# BarGraphDriver.net
KiCad netlist of a schematic drawn in EAGLE
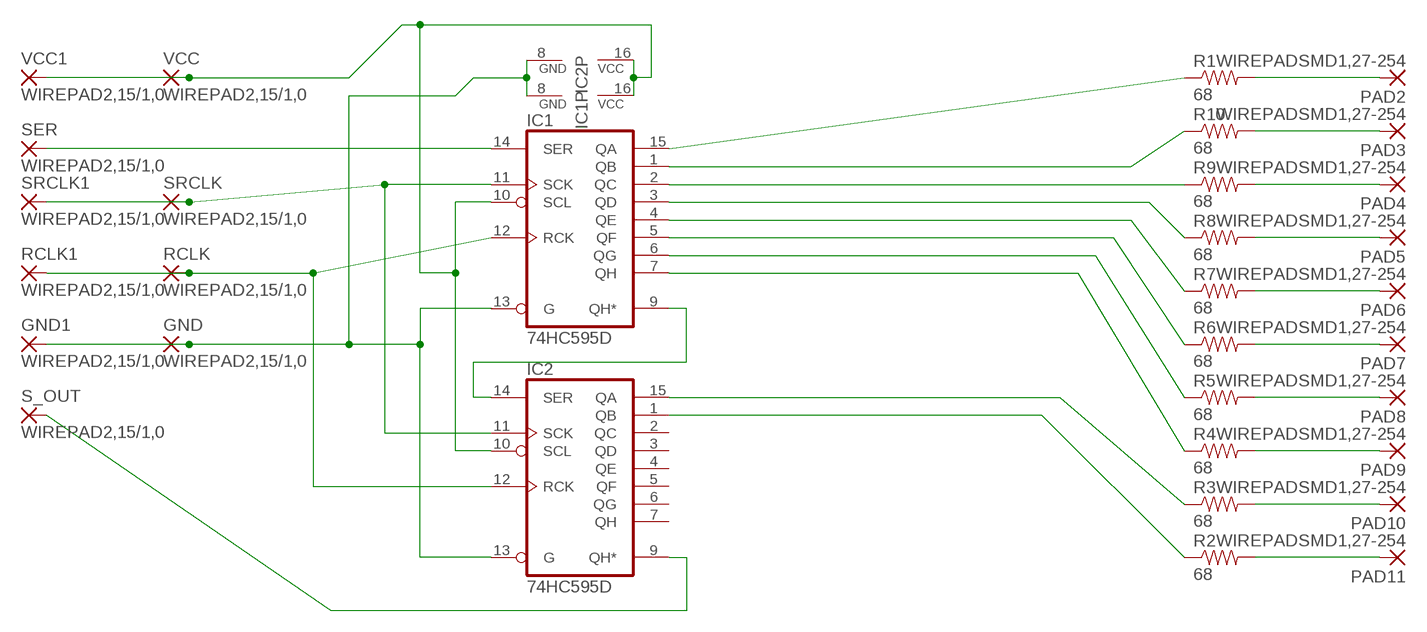
[diagram p0: schematic, sheet 1]

(export (version "E")
  (design (tool "Eeschema 10.0.6"))
  (components
    (comp (ref "GND")
      (value "WIREPAD2,15/1,0")
      (footprint "eagle-import:2,15_1,0")
      (libsource (lib "eagle-import") (part "wirepad_WIREPAD2,15/1,0"))
    )
    (comp (ref "GND1")
      (value "WIREPAD2,15/1,0")
      (footprint "eagle-import:2,15_1,0")
      (libsource (lib "eagle-import") (part "wirepad_WIREPAD2,15/1,0"))
    )
    (comp (ref "IC1")
      (value "74HC595D")
      (footprint "eagle-import:SO16")
      (libsource (lib "eagle-import") (part "74595DHC"))
    )
    (comp (ref "IC2")
      (value "74HC595D")
      (footprint "eagle-import:SO16")
      (libsource (lib "eagle-import") (part "74595DHC"))
    )
    (comp (ref "PAD2")
      (value "WIREPADSMD1,27-254")
      (footprint "eagle-import:SMD1,27-2,54")
      (libsource (lib "eagle-import") (part "wirepad_WIREPADSMD1,27-254"))
    )
    (comp (ref "PAD3")
      (value "WIREPADSMD1,27-254")
      (footprint "eagle-import:SMD1,27-2,54")
      (libsource (lib "eagle-import") (part "wirepad_WIREPADSMD1,27-254"))
    )
    (comp (ref "PAD4")
      (value "WIREPADSMD1,27-254")
      (footprint "eagle-import:SMD1,27-2,54")
      (libsource (lib "eagle-import") (part "wirepad_WIREPADSMD1,27-254"))
    )
    (comp (ref "PAD5")
      (value "WIREPADSMD1,27-254")
      (footprint "eagle-import:SMD1,27-2,54")
      (libsource (lib "eagle-import") (part "wirepad_WIREPADSMD1,27-254"))
    )
    (comp (ref "PAD6")
      (value "WIREPADSMD1,27-254")
      (footprint "eagle-import:SMD1,27-2,54")
      (libsource (lib "eagle-import") (part "wirepad_WIREPADSMD1,27-254"))
    )
    (comp (ref "PAD7")
      (value "WIREPADSMD1,27-254")
      (footprint "eagle-import:SMD1,27-2,54")
      (libsource (lib "eagle-import") (part "wirepad_WIREPADSMD1,27-254"))
    )
    (comp (ref "PAD8")
      (value "WIREPADSMD1,27-254")
      (footprint "eagle-import:SMD1,27-2,54")
      (libsource (lib "eagle-import") (part "wirepad_WIREPADSMD1,27-254"))
    )
    (comp (ref "PAD9")
      (value "WIREPADSMD1,27-254")
      (footprint "eagle-import:SMD1,27-2,54")
      (libsource (lib "eagle-import") (part "wirepad_WIREPADSMD1,27-254"))
    )
    (comp (ref "PAD10")
      (value "WIREPADSMD1,27-254")
      (footprint "eagle-import:SMD1,27-2,54")
      (libsource (lib "eagle-import") (part "wirepad_WIREPADSMD1,27-254"))
    )
    (comp (ref "PAD11")
      (value "WIREPADSMD1,27-254")
      (footprint "eagle-import:SMD1,27-2,54")
      (libsource (lib "eagle-import") (part "wirepad_WIREPADSMD1,27-254"))
    )
    (comp (ref "R1")
      (value "68")
      (footprint "eagle-import:1206")
      (libsource (lib "eagle-import") (part "RESISTOR1206"))
    )
    (comp (ref "R2")
      (value "68")
      (footprint "eagle-import:1206")
      (libsource (lib "eagle-import") (part "RESISTOR1206"))
    )
    (comp (ref "R3")
      (value "68")
      (footprint "eagle-import:1206")
      (libsource (lib "eagle-import") (part "RESISTOR1206"))
    )
    (comp (ref "R4")
      (value "68")
      (footprint "eagle-import:1206")
      (libsource (lib "eagle-import") (part "RESISTOR1206"))
    )
    (comp (ref "R5")
      (value "68")
      (footprint "eagle-import:1206")
      (libsource (lib "eagle-import") (part "RESISTOR1206"))
    )
    (comp (ref "R6")
      (value "68")
      (footprint "eagle-import:1206")
      (libsource (lib "eagle-import") (part "RESISTOR1206"))
    )
    (comp (ref "R7")
      (value "68")
      (footprint "eagle-import:1206")
      (libsource (lib "eagle-import") (part "RESISTOR1206"))
    )
    (comp (ref "R8")
      (value "68")
      (footprint "eagle-import:1206")
      (libsource (lib "eagle-import") (part "RESISTOR1206"))
    )
    (comp (ref "R9")
      (value "68")
      (footprint "eagle-import:1206")
      (libsource (lib "eagle-import") (part "RESISTOR1206"))
    )
    (comp (ref "R10")
      (value "68")
      (footprint "eagle-import:1206")
      (libsource (lib "eagle-import") (part "RESISTOR1206"))
    )
    (comp (ref "RCLK")
      (value "WIREPAD2,15/1,0")
      (footprint "eagle-import:2,15_1,0")
      (libsource (lib "eagle-import") (part "wirepad_WIREPAD2,15/1,0"))
    )
    (comp (ref "RCLK1")
      (value "WIREPAD2,15/1,0")
      (footprint "eagle-import:2,15_1,0")
      (libsource (lib "eagle-import") (part "wirepad_WIREPAD2,15/1,0"))
    )
    (comp (ref "SER")
      (value "WIREPAD2,15/1,0")
      (footprint "eagle-import:2,15_1,0")
      (libsource (lib "eagle-import") (part "wirepad_WIREPAD2,15/1,0"))
    )
    (comp (ref "SRCLK")
      (value "WIREPAD2,15/1,0")
      (footprint "eagle-import:2,15_1,0")
      (libsource (lib "eagle-import") (part "wirepad_WIREPAD2,15/1,0"))
    )
    (comp (ref "SRCLK1")
      (value "WIREPAD2,15/1,0")
      (footprint "eagle-import:2,15_1,0")
      (libsource (lib "eagle-import") (part "wirepad_WIREPAD2,15/1,0"))
    )
    (comp (ref "S_OUT")
      (value "WIREPAD2,15/1,0")
      (footprint "eagle-import:2,15_1,0")
      (libsource (lib "eagle-import") (part "wirepad_WIREPAD2,15/1,0"))
    )
    (comp (ref "VCC")
      (value "WIREPAD2,15/1,0")
      (footprint "eagle-import:2,15_1,0")
      (libsource (lib "eagle-import") (part "WIREPAD2,15/1,0"))
    )
    (comp (ref "VCC1")
      (value "WIREPAD2,15/1,0")
      (footprint "eagle-import:2,15_1,0")
      (libsource (lib "eagle-import") (part "WIREPAD2,15/1,0"))
    )
  )
  (nets
    (net (code "1") (name "Net-(GND-P)") (class "Default")
      (node (ref "GND") (pin "1") (pinfunction "P_1") (pintype "passive"))
      (node (ref "GND1") (pin "1") (pinfunction "P_1") (pintype "passive"))
      (node (ref "IC1") (pin "13") (pinfunction "G_13") (pintype "input"))
      (node (ref "IC1") (pin "8") (pinfunction "GND_8") (pintype "power_in"))
      (node (ref "IC2") (pin "13") (pinfunction "G_13") (pintype "input"))
      (node (ref "IC2") (pin "8") (pinfunction "GND_8") (pintype "power_in"))
    )
    (net (code "2") (name "Net-(IC1A-QA)") (class "Default")
      (node (ref "IC1") (pin "15") (pinfunction "QA_15") (pintype "tri_state"))
      (node (ref "R1") (pin "1") (pinfunction "1_1") (pintype "passive"))
    )
    (net (code "3") (name "Net-(IC1A-QB)") (class "Default")
      (node (ref "IC1") (pin "1") (pinfunction "QB_1") (pintype "tri_state"))
      (node (ref "R10") (pin "1") (pinfunction "1_1") (pintype "passive"))
    )
    (net (code "4") (name "Net-(IC1A-QC)") (class "Default")
      (node (ref "IC1") (pin "2") (pinfunction "QC_2") (pintype "tri_state"))
      (node (ref "R9") (pin "1") (pinfunction "1_1") (pintype "passive"))
    )
    (net (code "5") (name "Net-(IC1A-QD)") (class "Default")
      (node (ref "IC1") (pin "3") (pinfunction "QD_3") (pintype "tri_state"))
      (node (ref "R8") (pin "1") (pinfunction "1_1") (pintype "passive"))
    )
    (net (code "6") (name "Net-(IC1A-QE)") (class "Default")
      (node (ref "IC1") (pin "4") (pinfunction "QE_4") (pintype "tri_state"))
      (node (ref "R7") (pin "1") (pinfunction "1_1") (pintype "passive"))
    )
    (net (code "7") (name "Net-(IC1A-QF)") (class "Default")
      (node (ref "IC1") (pin "5") (pinfunction "QF_5") (pintype "tri_state"))
      (node (ref "R6") (pin "1") (pinfunction "1_1") (pintype "passive"))
    )
    (net (code "8") (name "Net-(IC1A-QG)") (class "Default")
      (node (ref "IC1") (pin "6") (pinfunction "QG_6") (pintype "tri_state"))
      (node (ref "R5") (pin "1") (pinfunction "1_1") (pintype "passive"))
    )
    (net (code "9") (name "Net-(IC1A-QH)") (class "Default")
      (node (ref "IC1") (pin "7") (pinfunction "QH_7") (pintype "tri_state"))
      (node (ref "R4") (pin "1") (pinfunction "1_1") (pintype "passive"))
    )
    (net (code "10") (name "Net-(IC1A-QH*)") (class "Default")
      (node (ref "IC1") (pin "9") (pinfunction "QH*_9") (pintype "tri_state"))
      (node (ref "IC2") (pin "14") (pinfunction "SER_14") (pintype "input"))
    )
    (net (code "11") (name "Net-(IC1A-RCK)") (class "Default")
      (node (ref "IC1") (pin "12") (pinfunction "RCK_12") (pintype "input"))
      (node (ref "IC2") (pin "12") (pinfunction "RCK_12") (pintype "input"))
      (node (ref "RCLK") (pin "1") (pinfunction "P_1") (pintype "passive"))
      (node (ref "RCLK1") (pin "1") (pinfunction "P_1") (pintype "passive"))
    )
    (net (code "12") (name "Net-(IC1A-SCK)") (class "Default")
      (node (ref "IC1") (pin "11") (pinfunction "SCK_11") (pintype "input"))
      (node (ref "IC2") (pin "11") (pinfunction "SCK_11") (pintype "input"))
      (node (ref "SRCLK") (pin "1") (pinfunction "P_1") (pintype "passive"))
      (node (ref "SRCLK1") (pin "1") (pinfunction "P_1") (pintype "passive"))
    )
    (net (code "13") (name "Net-(IC1A-SCL)") (class "Default")
      (node (ref "IC1") (pin "10") (pinfunction "SCL_10") (pintype "input"))
      (node (ref "IC1") (pin "16") (pinfunction "VCC_16") (pintype "power_in"))
      (node (ref "IC2") (pin "10") (pinfunction "SCL_10") (pintype "input"))
      (node (ref "IC2") (pin "16") (pinfunction "VCC_16") (pintype "power_in"))
      (node (ref "VCC") (pin "1") (pinfunction "P_1") (pintype "passive"))
      (node (ref "VCC1") (pin "1") (pinfunction "P_1") (pintype "passive"))
    )
    (net (code "14") (name "Net-(IC1A-SER)") (class "Default")
      (node (ref "IC1") (pin "14") (pinfunction "SER_14") (pintype "input"))
      (node (ref "SER") (pin "1") (pinfunction "P_1") (pintype "passive"))
    )
    (net (code "15") (name "Net-(IC2A-QA)") (class "Default")
      (node (ref "IC2") (pin "15") (pinfunction "QA_15") (pintype "tri_state"))
      (node (ref "R3") (pin "1") (pinfunction "1_1") (pintype "passive"))
    )
    (net (code "16") (name "Net-(IC2A-QB)") (class "Default")
      (node (ref "IC2") (pin "1") (pinfunction "QB_1") (pintype "tri_state"))
      (node (ref "R2") (pin "1") (pinfunction "1_1") (pintype "passive"))
    )
    (net (code "17") (name "Net-(IC2A-QH*)") (class "Default")
      (node (ref "IC2") (pin "9") (pinfunction "QH*_9") (pintype "tri_state"))
      (node (ref "S_OUT") (pin "1") (pinfunction "P_1") (pintype "passive"))
    )
    (net (code "18") (name "Net-(PAD2-P)") (class "Default")
      (node (ref "PAD2") (pin "1") (pinfunction "P_1") (pintype "passive"))
      (node (ref "R1") (pin "2") (pinfunction "2_2") (pintype "passive"))
    )
    (net (code "19") (name "Net-(PAD3-P)") (class "Default")
      (node (ref "PAD3") (pin "1") (pinfunction "P_1") (pintype "passive"))
      (node (ref "R10") (pin "2") (pinfunction "2_2") (pintype "passive"))
    )
    (net (code "20") (name "Net-(PAD4-P)") (class "Default")
      (node (ref "PAD4") (pin "1") (pinfunction "P_1") (pintype "passive"))
      (node (ref "R9") (pin "2") (pinfunction "2_2") (pintype "passive"))
    )
    (net (code "21") (name "Net-(PAD5-P)") (class "Default")
      (node (ref "PAD5") (pin "1") (pinfunction "P_1") (pintype "passive"))
      (node (ref "R8") (pin "2") (pinfunction "2_2") (pintype "passive"))
    )
    (net (code "22") (name "Net-(PAD6-P)") (class "Default")
      (node (ref "PAD6") (pin "1") (pinfunction "P_1") (pintype "passive"))
      (node (ref "R7") (pin "2") (pinfunction "2_2") (pintype "passive"))
    )
    (net (code "23") (name "Net-(PAD7-P)") (class "Default")
      (node (ref "PAD7") (pin "1") (pinfunction "P_1") (pintype "passive"))
      (node (ref "R6") (pin "2") (pinfunction "2_2") (pintype "passive"))
    )
    (net (code "24") (name "Net-(PAD8-P)") (class "Default")
      (node (ref "PAD8") (pin "1") (pinfunction "P_1") (pintype "passive"))
      (node (ref "R5") (pin "2") (pinfunction "2_2") (pintype "passive"))
    )
    (net (code "25") (name "Net-(PAD9-P)") (class "Default")
      (node (ref "PAD9") (pin "1") (pinfunction "P_1") (pintype "passive"))
      (node (ref "R4") (pin "2") (pinfunction "2_2") (pintype "passive"))
    )
    (net (code "26") (name "Net-(PAD10-P)") (class "Default")
      (node (ref "PAD10") (pin "1") (pinfunction "P_1") (pintype "passive"))
      (node (ref "R3") (pin "2") (pinfunction "2_2") (pintype "passive"))
    )
    (net (code "27") (name "Net-(PAD11-P)") (class "Default")
      (node (ref "PAD11") (pin "1") (pinfunction "P_1") (pintype "passive"))
      (node (ref "R2") (pin "2") (pinfunction "2_2") (pintype "passive"))
    )
    (net (code "28") (name "unconnected-(IC2A-QC-Pad2)") (class "Default")
      (node (ref "IC2") (pin "2") (pinfunction "QC_2") (pintype "tri_state"))
    )
    (net (code "29") (name "unconnected-(IC2A-QD-Pad3)") (class "Default")
      (node (ref "IC2") (pin "3") (pinfunction "QD_3") (pintype "tri_state"))
    )
    (net (code "30") (name "unconnected-(IC2A-QE-Pad4)") (class "Default")
      (node (ref "IC2") (pin "4") (pinfunction "QE_4") (pintype "tri_state"))
    )
    (net (code "31") (name "unconnected-(IC2A-QF-Pad5)") (class "Default")
      (node (ref "IC2") (pin "5") (pinfunction "QF_5") (pintype "tri_state"))
    )
    (net (code "32") (name "unconnected-(IC2A-QG-Pad6)") (class "Default")
      (node (ref "IC2") (pin "6") (pinfunction "QG_6") (pintype "tri_state"))
    )
    (net (code "33") (name "unconnected-(IC2A-QH-Pad7)") (class "Default")
      (node (ref "IC2") (pin "7") (pinfunction "QH_7") (pintype "tri_state"))
    )
  )
)
